# Half_Bridges.net
KiCad netlist of a schematic drawn in Altium Designer
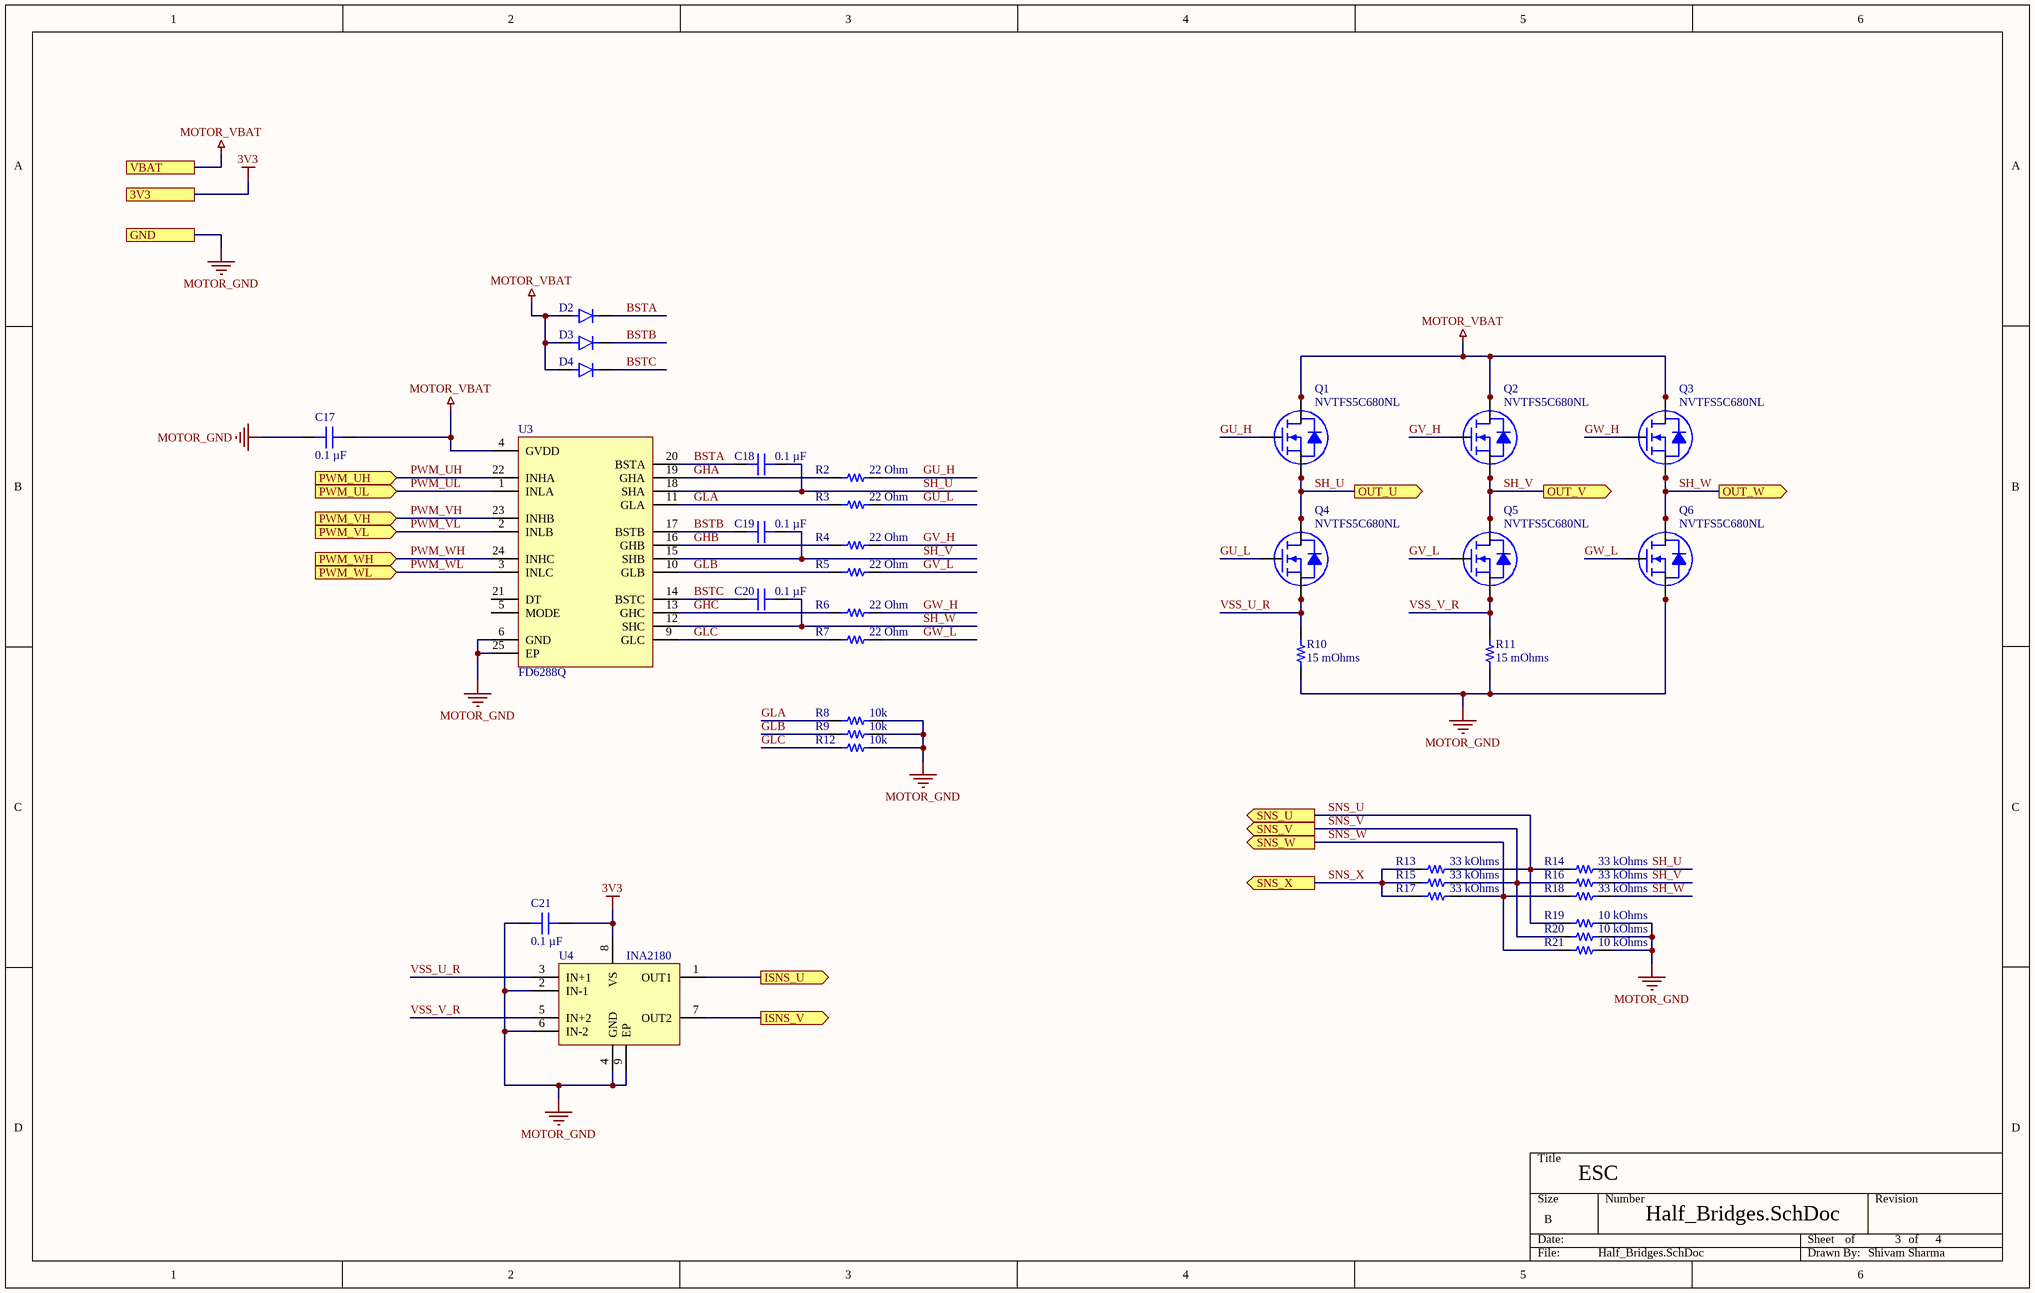
[diagram p0: Half_Bridges.SchDoc]

(export (version "E")
  (design (tool "Eeschema 10.0.6"))
  (components
    (comp (ref "C17")
      (value "0.1 µF")
      (footprint "CAP 0402_1005")
      (description "CAP CER 0.1UF 16V X7R 0402")
      (fields (field (name "PART NUMBER") "C0402C104K4RACAUTO") (field (name "MANUFACTURER") "KEMET"))
      (libsource (lib "Celestial Altium Library - altium_library") (part "Capacitor"))
    )
    (comp (ref "C18")
      (value "0.1 µF")
      (footprint "CAP 0402_1005")
      (description "CAP CER 0.1UF 16V X7R 0402")
      (fields (field (name "PART NUMBER") "C0402C104K4RACAUTO") (field (name "MANUFACTURER") "KEMET"))
      (libsource (lib "Celestial Altium Library - altium_library") (part "Capacitor"))
    )
    (comp (ref "C19")
      (value "0.1 µF")
      (footprint "CAP 0402_1005")
      (description "CAP CER 0.1UF 16V X7R 0402")
      (fields (field (name "PART NUMBER") "C0402C104K4RACAUTO") (field (name "MANUFACTURER") "KEMET"))
      (libsource (lib "Celestial Altium Library - altium_library") (part "Capacitor"))
    )
    (comp (ref "C20")
      (value "0.1 µF")
      (footprint "CAP 0402_1005")
      (description "CAP CER 0.1UF 16V X7R 0402")
      (fields (field (name "PART NUMBER") "C0402C104K4RACAUTO") (field (name "MANUFACTURER") "KEMET"))
      (libsource (lib "Celestial Altium Library - altium_library") (part "Capacitor"))
    )
    (comp (ref "C21")
      (value "0.1 µF")
      (footprint "CAP 0402_1005")
      (description "CAP CER 0.1UF 16V X7R 0402")
      (fields (field (name "PART NUMBER") "C0402C104K4RACAUTO") (field (name "MANUFACTURER") "KEMET"))
      (libsource (lib "Celestial Altium Library - altium_library") (part "Capacitor"))
    )
    (comp (ref "D2")
      (value "Diode")
      (footprint "Diode DFN1608D-2 (SOD1608)")
      (description "DFN1608D-2 (SOD1608)")
      (fields (field (name "MANUFACTURER") "Cree") (field (name "MOUSER PART NUMBER") "941-CLV1LFKBC7673673"))
      (libsource (lib "IC") (part "Diode"))
    )
    (comp (ref "D3")
      (value "Diode")
      (footprint "Diode DFN1608D-2 (SOD1608)")
      (description "DFN1608D-2 (SOD1608)")
      (fields (field (name "MANUFACTURER") "Cree") (field (name "MOUSER PART NUMBER") "941-CLV1LFKBC7673673"))
      (libsource (lib "IC") (part "Diode"))
    )
    (comp (ref "D4")
      (value "Diode")
      (footprint "Diode DFN1608D-2 (SOD1608)")
      (description "DFN1608D-2 (SOD1608)")
      (fields (field (name "MANUFACTURER") "Cree") (field (name "MOUSER PART NUMBER") "941-CLV1LFKBC7673673"))
      (libsource (lib "IC") (part "Diode"))
    )
    (comp (ref "Q1")
      (value "NVTFS5C680NL")
      (footprint "NVTFS015N04CTAG")
      (description "N-FET")
      (libsource (lib "IC") (part "NVTFS5C680NL"))
    )
    (comp (ref "Q2")
      (value "NVTFS5C680NL")
      (footprint "NVTFS015N04CTAG")
      (description "N-FET")
      (libsource (lib "IC") (part "NVTFS5C680NL"))
    )
    (comp (ref "Q3")
      (value "NVTFS5C680NL")
      (footprint "NVTFS015N04CTAG")
      (description "N-FET")
      (libsource (lib "IC") (part "NVTFS5C680NL"))
    )
    (comp (ref "Q4")
      (value "NVTFS5C680NL")
      (footprint "NVTFS015N04CTAG")
      (description "N-FET")
      (libsource (lib "IC") (part "NVTFS5C680NL"))
    )
    (comp (ref "Q5")
      (value "NVTFS5C680NL")
      (footprint "NVTFS015N04CTAG")
      (description "N-FET")
      (libsource (lib "IC") (part "NVTFS5C680NL"))
    )
    (comp (ref "Q6")
      (value "NVTFS5C680NL")
      (footprint "NVTFS015N04CTAG")
      (description "N-FET")
      (libsource (lib "IC") (part "NVTFS5C680NL"))
    )
    (comp (ref "R2")
      (value "22 Ohm")
      (footprint "RES 0402_1005")
      (description "RES 14.3K OHM 1% 1/10W 0402")
      (fields
        (field (name "PART NUMBER") "RK73H1ETTP1432F")
        (field (name "MANUFACTURER") "KOA Speer Electronics, Inc.")
      )
      (libsource (lib "Celestial Altium Library - altium_library") (part "Resistor"))
    )
    (comp (ref "R3")
      (value "22 Ohm")
      (footprint "RES 0402_1005")
      (description "RES 14.3K OHM 1% 1/10W 0402")
      (fields
        (field (name "PART NUMBER") "RK73H1ETTP1432F")
        (field (name "MANUFACTURER") "KOA Speer Electronics, Inc.")
      )
      (libsource (lib "Celestial Altium Library - altium_library") (part "Resistor"))
    )
    (comp (ref "R4")
      (value "22 Ohm")
      (footprint "RES 0402_1005")
      (description "RES 14.3K OHM 1% 1/10W 0402")
      (fields
        (field (name "PART NUMBER") "RK73H1ETTP1432F")
        (field (name "MANUFACTURER") "KOA Speer Electronics, Inc.")
      )
      (libsource (lib "Celestial Altium Library - altium_library") (part "Resistor"))
    )
    (comp (ref "R5")
      (value "22 Ohm")
      (footprint "RES 0402_1005")
      (description "RES 14.3K OHM 1% 1/10W 0402")
      (fields
        (field (name "PART NUMBER") "RK73H1ETTP1432F")
        (field (name "MANUFACTURER") "KOA Speer Electronics, Inc.")
      )
      (libsource (lib "Celestial Altium Library - altium_library") (part "Resistor"))
    )
    (comp (ref "R6")
      (value "22 Ohm")
      (footprint "RES 0402_1005")
      (description "RES 14.3K OHM 1% 1/10W 0402")
      (fields
        (field (name "PART NUMBER") "RK73H1ETTP1432F")
        (field (name "MANUFACTURER") "KOA Speer Electronics, Inc.")
      )
      (libsource (lib "Celestial Altium Library - altium_library") (part "Resistor"))
    )
    (comp (ref "R7")
      (value "22 Ohm")
      (footprint "RES 0402_1005")
      (description "RES 14.3K OHM 1% 1/10W 0402")
      (fields
        (field (name "PART NUMBER") "RK73H1ETTP1432F")
        (field (name "MANUFACTURER") "KOA Speer Electronics, Inc.")
      )
      (libsource (lib "Celestial Altium Library - altium_library") (part "Resistor"))
    )
    (comp (ref "R8")
      (value "10k")
      (footprint "RES 0402_1005")
      (description "RES 14.3K OHM 1% 1/10W 0402")
      (fields
        (field (name "PART NUMBER") "RK73H1ETTP1432F")
        (field (name "MANUFACTURER") "KOA Speer Electronics, Inc.")
      )
      (libsource (lib "Celestial Altium Library - altium_library") (part "Resistor"))
    )
    (comp (ref "R9")
      (value "10k")
      (footprint "RES 0402_1005")
      (description "RES 14.3K OHM 1% 1/10W 0402")
      (fields
        (field (name "PART NUMBER") "RK73H1ETTP1432F")
        (field (name "MANUFACTURER") "KOA Speer Electronics, Inc.")
      )
      (libsource (lib "Celestial Altium Library - altium_library") (part "Resistor"))
    )
    (comp (ref "R10")
      (value "15 mOhms")
      (footprint "RES 0805_2012")
      (description "RES SMD 20K OHM 0.1% 1W 0805")
      (fields
        (field (name "PART NUMBER") "PCAN0805E2002BST5")
        (field (name "MANUFACTURER") "Vishay Thin Film")
      )
      (libsource (lib "Celestial Altium Library - altium_library") (part "Resistor"))
    )
    (comp (ref "R11")
      (value "15 mOhms")
      (footprint "RES 0805_2012")
      (description "RES SMD 20K OHM 0.1% 1W 0805")
      (fields
        (field (name "PART NUMBER") "PCAN0805E2002BST5")
        (field (name "MANUFACTURER") "Vishay Thin Film")
      )
      (libsource (lib "Celestial Altium Library - altium_library") (part "Resistor"))
    )
    (comp (ref "R12")
      (value "10k")
      (footprint "RES 0402_1005")
      (description "RES 14.3K OHM 1% 1/10W 0402")
      (fields
        (field (name "PART NUMBER") "RK73H1ETTP1432F")
        (field (name "MANUFACTURER") "KOA Speer Electronics, Inc.")
      )
      (libsource (lib "Celestial Altium Library - altium_library") (part "Resistor"))
    )
    (comp (ref "R13")
      (value "33 kOhms")
      (footprint "RES 0402_1005")
      (description "RES 14.3K OHM 1% 1/10W 0402")
      (fields
        (field (name "PART NUMBER") "RK73H1ETTP1432F")
        (field (name "MANUFACTURER") "KOA Speer Electronics, Inc.")
      )
      (libsource (lib "Celestial Altium Library - altium_library") (part "Resistor"))
    )
    (comp (ref "R14")
      (value "33 kOhms")
      (footprint "RES 0402_1005")
      (description "RES 14.3K OHM 1% 1/10W 0402")
      (fields
        (field (name "PART NUMBER") "RK73H1ETTP1432F")
        (field (name "MANUFACTURER") "KOA Speer Electronics, Inc.")
      )
      (libsource (lib "Celestial Altium Library - altium_library") (part "Resistor"))
    )
    (comp (ref "R15")
      (value "33 kOhms")
      (footprint "RES 0402_1005")
      (description "RES 14.3K OHM 1% 1/10W 0402")
      (fields
        (field (name "PART NUMBER") "RK73H1ETTP1432F")
        (field (name "MANUFACTURER") "KOA Speer Electronics, Inc.")
      )
      (libsource (lib "Celestial Altium Library - altium_library") (part "Resistor"))
    )
    (comp (ref "R16")
      (value "33 kOhms")
      (footprint "RES 0402_1005")
      (description "RES 14.3K OHM 1% 1/10W 0402")
      (fields
        (field (name "PART NUMBER") "RK73H1ETTP1432F")
        (field (name "MANUFACTURER") "KOA Speer Electronics, Inc.")
      )
      (libsource (lib "Celestial Altium Library - altium_library") (part "Resistor"))
    )
    (comp (ref "R17")
      (value "33 kOhms")
      (footprint "RES 0402_1005")
      (description "RES 14.3K OHM 1% 1/10W 0402")
      (fields
        (field (name "PART NUMBER") "RK73H1ETTP1432F")
        (field (name "MANUFACTURER") "KOA Speer Electronics, Inc.")
      )
      (libsource (lib "Celestial Altium Library - altium_library") (part "Resistor"))
    )
    (comp (ref "R18")
      (value "33 kOhms")
      (footprint "RES 0402_1005")
      (description "RES 14.3K OHM 1% 1/10W 0402")
      (fields
        (field (name "PART NUMBER") "RK73H1ETTP1432F")
        (field (name "MANUFACTURER") "KOA Speer Electronics, Inc.")
      )
      (libsource (lib "Celestial Altium Library - altium_library") (part "Resistor"))
    )
    (comp (ref "R19")
      (value "10 kOhms")
      (footprint "RES 0402_1005")
      (description "RES 14.3K OHM 1% 1/10W 0402")
      (fields
        (field (name "PART NUMBER") "RK73H1ETTP1432F")
        (field (name "MANUFACTURER") "KOA Speer Electronics, Inc.")
      )
      (libsource (lib "Celestial Altium Library - altium_library") (part "Resistor"))
    )
    (comp (ref "R20")
      (value "10 kOhms")
      (footprint "RES 0402_1005")
      (description "RES 14.3K OHM 1% 1/10W 0402")
      (fields
        (field (name "PART NUMBER") "RK73H1ETTP1432F")
        (field (name "MANUFACTURER") "KOA Speer Electronics, Inc.")
      )
      (libsource (lib "Celestial Altium Library - altium_library") (part "Resistor"))
    )
    (comp (ref "R21")
      (value "10 kOhms")
      (footprint "RES 0402_1005")
      (description "RES 14.3K OHM 1% 1/10W 0402")
      (fields
        (field (name "PART NUMBER") "RK73H1ETTP1432F")
        (field (name "MANUFACTURER") "KOA Speer Electronics, Inc.")
      )
      (libsource (lib "Celestial Altium Library - altium_library") (part "Resistor"))
    )
    (comp (ref "U3")
      (value "FD6288Q")
      (footprint "QFN50P400X400X100-25N")
      (description "3 Phase Gate Driver 1.5-2.2A")
      (fields (field (name "MF") "Texas Instruments") (field (name "MP") "UCC27282DRCR"))
      (libsource (lib "IC") (part "FD6288Q"))
    )
    (comp (ref "U4")
      (value "INA2180")
      (footprint "WSON-8_2x2")
      (description "Current sense amplifier 4 channel")
      (libsource (lib "IC") (part "INA2180"))
    )
  )
  (nets
    (net (code "1") (name "/BSTA") (class "Default")
      (node (ref "C18") (pin "1") (pinfunction "1_1") (pintype "passive"))
      (node (ref "D2") (pin "1") (pinfunction "A_1") (pintype "passive"))
      (node (ref "U3") (pin "20") (pinfunction "BSTA_20") (pintype "passive"))
    )
    (net (code "2") (name "/BSTB") (class "Default")
      (node (ref "C19") (pin "1") (pinfunction "1_1") (pintype "passive"))
      (node (ref "D3") (pin "1") (pinfunction "A_1") (pintype "passive"))
      (node (ref "U3") (pin "17") (pinfunction "BSTB_17") (pintype "passive"))
    )
    (net (code "3") (name "/BSTC") (class "Default")
      (node (ref "C20") (pin "1") (pinfunction "1_1") (pintype "passive"))
      (node (ref "D4") (pin "1") (pinfunction "A_1") (pintype "passive"))
      (node (ref "U3") (pin "14") (pinfunction "BSTC_14") (pintype "passive"))
    )
    (net (code "4") (name "/GHA") (class "Default")
      (node (ref "R2") (pin "1") (pinfunction "1_1") (pintype "passive"))
      (node (ref "U3") (pin "19") (pinfunction "GHA_19") (pintype "passive"))
    )
    (net (code "5") (name "/GHB") (class "Default")
      (node (ref "R4") (pin "1") (pinfunction "1_1") (pintype "passive"))
      (node (ref "U3") (pin "16") (pinfunction "GHB_16") (pintype "passive"))
    )
    (net (code "6") (name "/GHC") (class "Default")
      (node (ref "R6") (pin "1") (pinfunction "1_1") (pintype "passive"))
      (node (ref "U3") (pin "13") (pinfunction "GHC_13") (pintype "passive"))
    )
    (net (code "7") (name "/GLA") (class "Default")
      (node (ref "R3") (pin "1") (pinfunction "1_1") (pintype "passive"))
      (node (ref "R8") (pin "1") (pinfunction "1_1") (pintype "passive"))
      (node (ref "U3") (pin "11") (pinfunction "GLA_11") (pintype "passive"))
    )
    (net (code "8") (name "/GLB") (class "Default")
      (node (ref "R5") (pin "1") (pinfunction "1_1") (pintype "passive"))
      (node (ref "R9") (pin "1") (pinfunction "1_1") (pintype "passive"))
      (node (ref "U3") (pin "10") (pinfunction "GLB_10") (pintype "passive"))
    )
    (net (code "9") (name "/GLC") (class "Default")
      (node (ref "R12") (pin "1") (pinfunction "1_1") (pintype "passive"))
      (node (ref "R7") (pin "1") (pinfunction "1_1") (pintype "passive"))
      (node (ref "U3") (pin "9") (pinfunction "GLC_9") (pintype "passive"))
    )
    (net (code "10") (name "/GU_H") (class "Default")
      (node (ref "Q1") (pin "4") (pinfunction "G_4") (pintype "passive"))
      (node (ref "R2") (pin "2") (pinfunction "2_2") (pintype "passive"))
    )
    (net (code "11") (name "/GU_L") (class "Default")
      (node (ref "Q4") (pin "4") (pinfunction "G_4") (pintype "passive"))
      (node (ref "R3") (pin "2") (pinfunction "2_2") (pintype "passive"))
    )
    (net (code "12") (name "/GV_H") (class "Default")
      (node (ref "Q2") (pin "4") (pinfunction "G_4") (pintype "passive"))
      (node (ref "R4") (pin "2") (pinfunction "2_2") (pintype "passive"))
    )
    (net (code "13") (name "/GV_L") (class "Default")
      (node (ref "Q5") (pin "4") (pinfunction "G_4") (pintype "passive"))
      (node (ref "R5") (pin "2") (pinfunction "2_2") (pintype "passive"))
    )
    (net (code "14") (name "/GW_H") (class "Default")
      (node (ref "Q3") (pin "4") (pinfunction "G_4") (pintype "passive"))
      (node (ref "R6") (pin "2") (pinfunction "2_2") (pintype "passive"))
    )
    (net (code "15") (name "/GW_L") (class "Default")
      (node (ref "Q6") (pin "4") (pinfunction "G_4") (pintype "passive"))
      (node (ref "R7") (pin "2") (pinfunction "2_2") (pintype "passive"))
    )
    (net (code "16") (name "/ISNS_U") (class "Default")
      (node (ref "U4") (pin "1") (pinfunction "OUT1_1") (pintype "passive"))
    )
    (net (code "17") (name "/ISNS_V") (class "Default")
      (node (ref "U4") (pin "7") (pinfunction "OUT2_7") (pintype "passive"))
    )
    (net (code "18") (name "/PWM_UH") (class "Default")
      (node (ref "U3") (pin "22") (pinfunction "INHA_22") (pintype "passive"))
    )
    (net (code "19") (name "/PWM_UL") (class "Default")
      (node (ref "U3") (pin "1") (pinfunction "INLA_1") (pintype "passive"))
    )
    (net (code "20") (name "/PWM_VH") (class "Default")
      (node (ref "U3") (pin "23") (pinfunction "INHB_23") (pintype "passive"))
    )
    (net (code "21") (name "/PWM_VL") (class "Default")
      (node (ref "U3") (pin "2") (pinfunction "INLB_2") (pintype "passive"))
    )
    (net (code "22") (name "/PWM_WH") (class "Default")
      (node (ref "U3") (pin "24") (pinfunction "INHC_24") (pintype "passive"))
    )
    (net (code "23") (name "/PWM_WL") (class "Default")
      (node (ref "U3") (pin "3") (pinfunction "INLC_3") (pintype "passive"))
    )
    (net (code "24") (name "/SH_U") (class "Default")
      (node (ref "C18") (pin "2") (pinfunction "2_2") (pintype "passive"))
      (node (ref "Q1") (pin "1") (pinfunction "S_1") (pintype "passive"))
      (node (ref "Q1") (pin "2") (pinfunction "S_2") (pintype "passive"))
      (node (ref "Q1") (pin "3") (pinfunction "S_3") (pintype "passive"))
      (node (ref "Q4") (pin "5") (pinfunction "D_5") (pintype "passive"))
      (node (ref "Q4") (pin "6") (pinfunction "D_6") (pintype "passive"))
      (node (ref "Q4") (pin "7") (pinfunction "D_7") (pintype "passive"))
      (node (ref "Q4") (pin "8") (pinfunction "D_8") (pintype "passive"))
      (node (ref "R14") (pin "2") (pinfunction "2_2") (pintype "passive"))
      (node (ref "U3") (pin "18") (pinfunction "SHA_18") (pintype "passive"))
    )
    (net (code "25") (name "/SH_V") (class "Default")
      (node (ref "C19") (pin "2") (pinfunction "2_2") (pintype "passive"))
      (node (ref "Q2") (pin "1") (pinfunction "S_1") (pintype "passive"))
      (node (ref "Q2") (pin "2") (pinfunction "S_2") (pintype "passive"))
      (node (ref "Q2") (pin "3") (pinfunction "S_3") (pintype "passive"))
      (node (ref "Q5") (pin "5") (pinfunction "D_5") (pintype "passive"))
      (node (ref "Q5") (pin "6") (pinfunction "D_6") (pintype "passive"))
      (node (ref "Q5") (pin "7") (pinfunction "D_7") (pintype "passive"))
      (node (ref "Q5") (pin "8") (pinfunction "D_8") (pintype "passive"))
      (node (ref "R16") (pin "2") (pinfunction "2_2") (pintype "passive"))
      (node (ref "U3") (pin "15") (pinfunction "SHB_15") (pintype "passive"))
    )
    (net (code "26") (name "/SH_W") (class "Default")
      (node (ref "C20") (pin "2") (pinfunction "2_2") (pintype "passive"))
      (node (ref "Q3") (pin "1") (pinfunction "S_1") (pintype "passive"))
      (node (ref "Q3") (pin "2") (pinfunction "S_2") (pintype "passive"))
      (node (ref "Q3") (pin "3") (pinfunction "S_3") (pintype "passive"))
      (node (ref "Q6") (pin "5") (pinfunction "D_5") (pintype "passive"))
      (node (ref "Q6") (pin "6") (pinfunction "D_6") (pintype "passive"))
      (node (ref "Q6") (pin "7") (pinfunction "D_7") (pintype "passive"))
      (node (ref "Q6") (pin "8") (pinfunction "D_8") (pintype "passive"))
      (node (ref "R18") (pin "2") (pinfunction "2_2") (pintype "passive"))
      (node (ref "U3") (pin "12") (pinfunction "SHC_12") (pintype "passive"))
    )
    (net (code "27") (name "/SNS_U") (class "Default")
      (node (ref "R13") (pin "2") (pinfunction "2_2") (pintype "passive"))
      (node (ref "R14") (pin "1") (pinfunction "1_1") (pintype "passive"))
      (node (ref "R19") (pin "2") (pinfunction "2_2") (pintype "passive"))
    )
    (net (code "28") (name "/SNS_V") (class "Default")
      (node (ref "R15") (pin "2") (pinfunction "2_2") (pintype "passive"))
      (node (ref "R16") (pin "1") (pinfunction "1_1") (pintype "passive"))
      (node (ref "R20") (pin "2") (pinfunction "2_2") (pintype "passive"))
    )
    (net (code "29") (name "/SNS_W") (class "Default")
      (node (ref "R17") (pin "2") (pinfunction "2_2") (pintype "passive"))
      (node (ref "R18") (pin "1") (pinfunction "1_1") (pintype "passive"))
      (node (ref "R21") (pin "2") (pinfunction "2_2") (pintype "passive"))
    )
    (net (code "30") (name "/SNS_X") (class "Default")
      (node (ref "R13") (pin "1") (pinfunction "1_1") (pintype "passive"))
      (node (ref "R15") (pin "1") (pinfunction "1_1") (pintype "passive"))
      (node (ref "R17") (pin "1") (pinfunction "1_1") (pintype "passive"))
    )
    (net (code "31") (name "/VSS_U_R") (class "Default")
      (node (ref "Q4") (pin "1") (pinfunction "S_1") (pintype "passive"))
      (node (ref "Q4") (pin "2") (pinfunction "S_2") (pintype "passive"))
      (node (ref "Q4") (pin "3") (pinfunction "S_3") (pintype "passive"))
      (node (ref "R10") (pin "2") (pinfunction "2_2") (pintype "passive"))
      (node (ref "U4") (pin "3") (pinfunction "IN+1_3") (pintype "passive"))
    )
    (net (code "32") (name "/VSS_V_R") (class "Default")
      (node (ref "Q5") (pin "1") (pinfunction "S_1") (pintype "passive"))
      (node (ref "Q5") (pin "2") (pinfunction "S_2") (pintype "passive"))
      (node (ref "Q5") (pin "3") (pinfunction "S_3") (pintype "passive"))
      (node (ref "R11") (pin "2") (pinfunction "2_2") (pintype "passive"))
      (node (ref "U4") (pin "5") (pinfunction "IN+2_5") (pintype "passive"))
    )
    (net (code "33") (name "3V3") (class "Default")
      (node (ref "C21") (pin "1") (pinfunction "1_1") (pintype "passive"))
      (node (ref "U4") (pin "8") (pinfunction "VS_8") (pintype "passive"))
    )
    (net (code "34") (name "MOTOR_GND") (class "Default")
      (node (ref "C17") (pin "1") (pinfunction "1_1") (pintype "passive"))
      (node (ref "C21") (pin "2") (pinfunction "2_2") (pintype "passive"))
      (node (ref "Q6") (pin "1") (pinfunction "S_1") (pintype "passive"))
      (node (ref "Q6") (pin "2") (pinfunction "S_2") (pintype "passive"))
      (node (ref "Q6") (pin "3") (pinfunction "S_3") (pintype "passive"))
      (node (ref "R10") (pin "1") (pinfunction "1_1") (pintype "passive"))
      (node (ref "R11") (pin "1") (pinfunction "1_1") (pintype "passive"))
      (node (ref "R12") (pin "2") (pinfunction "2_2") (pintype "passive"))
      (node (ref "R19") (pin "1") (pinfunction "1_1") (pintype "passive"))
      (node (ref "R20") (pin "1") (pinfunction "1_1") (pintype "passive"))
      (node (ref "R21") (pin "1") (pinfunction "1_1") (pintype "passive"))
      (node (ref "R8") (pin "2") (pinfunction "2_2") (pintype "passive"))
      (node (ref "R9") (pin "2") (pinfunction "2_2") (pintype "passive"))
      (node (ref "U3") (pin "25") (pinfunction "EP_25") (pintype "passive"))
      (node (ref "U3") (pin "6") (pinfunction "GND_6") (pintype "passive"))
      (node (ref "U4") (pin "2") (pinfunction "IN-1_2") (pintype "passive"))
      (node (ref "U4") (pin "4") (pinfunction "GND_4") (pintype "passive"))
      (node (ref "U4") (pin "6") (pinfunction "IN-2_6") (pintype "passive"))
      (node (ref "U4") (pin "9") (pinfunction "EP_9") (pintype "passive"))
    )
    (net (code "35") (name "MOTOR_VBAT") (class "Default")
      (node (ref "C17") (pin "2") (pinfunction "2_2") (pintype "passive"))
      (node (ref "D2") (pin "2") (pinfunction "BLUE(C)_2") (pintype "passive"))
      (node (ref "D3") (pin "2") (pinfunction "BLUE(C)_2") (pintype "passive"))
      (node (ref "D4") (pin "2") (pinfunction "BLUE(C)_2") (pintype "passive"))
      (node (ref "Q1") (pin "5") (pinfunction "D_5") (pintype "passive"))
      (node (ref "Q1") (pin "6") (pinfunction "D_6") (pintype "passive"))
      (node (ref "Q1") (pin "7") (pinfunction "D_7") (pintype "passive"))
      (node (ref "Q1") (pin "8") (pinfunction "D_8") (pintype "passive"))
      (node (ref "Q2") (pin "5") (pinfunction "D_5") (pintype "passive"))
      (node (ref "Q2") (pin "6") (pinfunction "D_6") (pintype "passive"))
      (node (ref "Q2") (pin "7") (pinfunction "D_7") (pintype "passive"))
      (node (ref "Q2") (pin "8") (pinfunction "D_8") (pintype "passive"))
      (node (ref "Q3") (pin "5") (pinfunction "D_5") (pintype "passive"))
      (node (ref "Q3") (pin "6") (pinfunction "D_6") (pintype "passive"))
      (node (ref "Q3") (pin "7") (pinfunction "D_7") (pintype "passive"))
      (node (ref "Q3") (pin "8") (pinfunction "D_8") (pintype "passive"))
      (node (ref "U3") (pin "4") (pinfunction "GVDD_4") (pintype "passive"))
    )
    (net (code "36") (name "unconnected-(U3-DT-Pad21)") (class "Default")
      (node (ref "U3") (pin "21") (pinfunction "DT_21") (pintype "passive"))
    )
    (net (code "37") (name "unconnected-(U3-MODE-Pad5)") (class "Default")
      (node (ref "U3") (pin "5") (pinfunction "MODE_5") (pintype "passive"))
    )
  )
)
